# Channels_3_4.net
KiCad netlist of a schematic drawn in Altium Designer
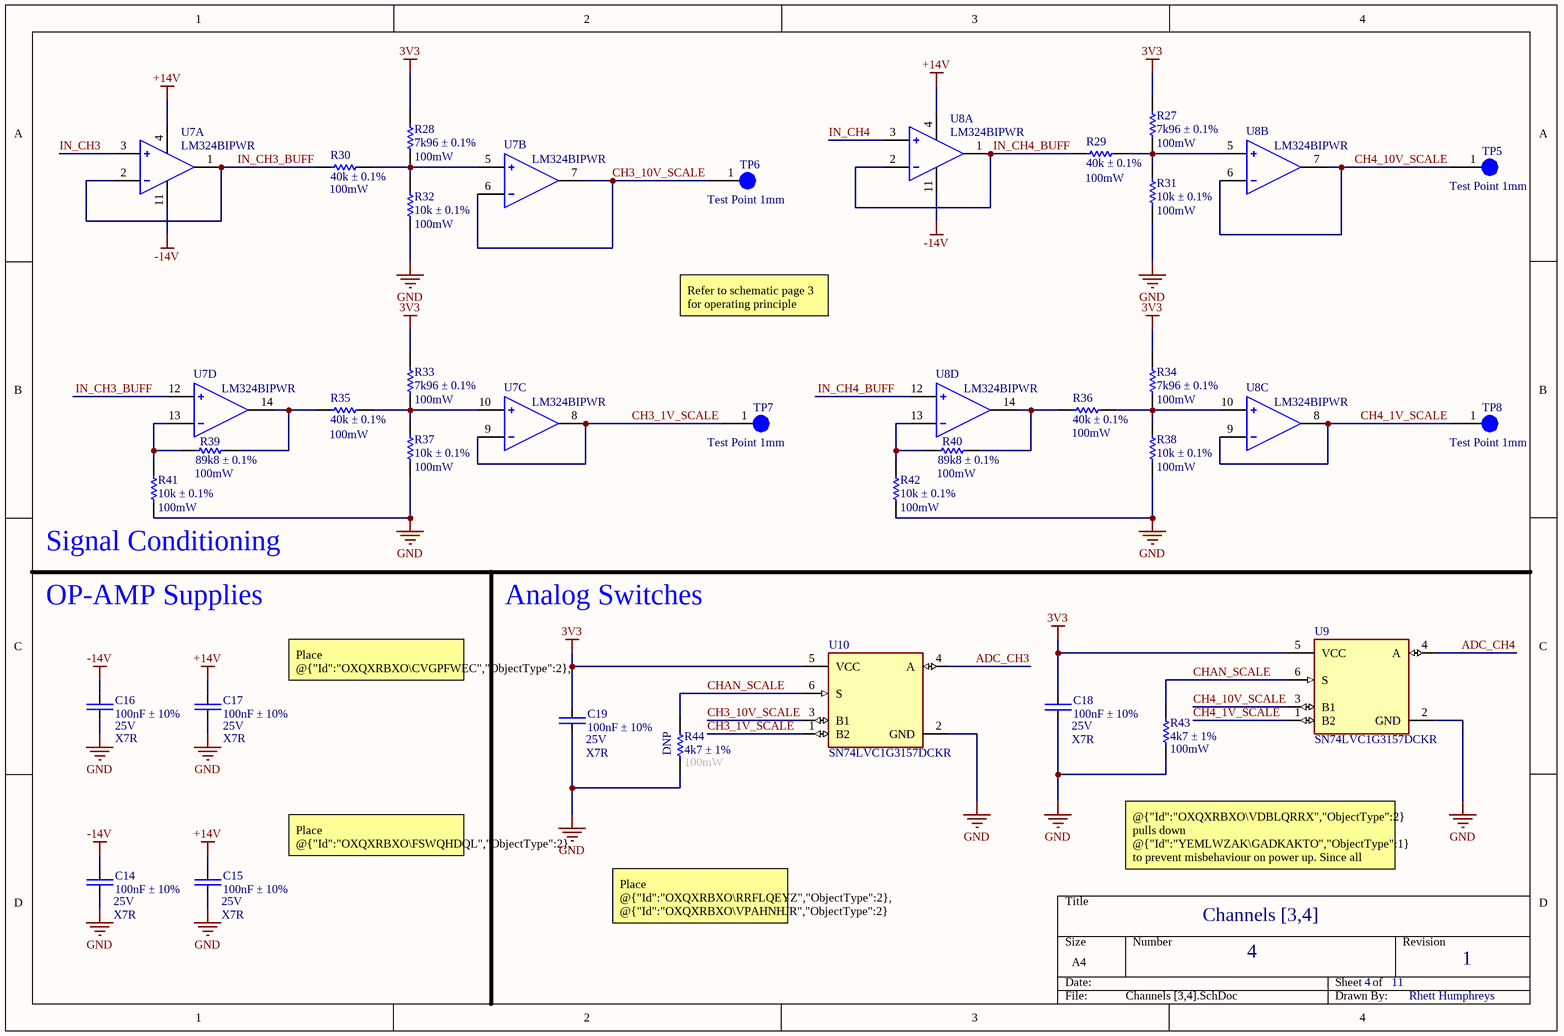
[diagram p0: Channels [3,4].SchDoc]

(export (version "E")
  (design (tool "Eeschema 10.0.6"))
  (components
    (comp (ref "C14")
      (value "100nF ± 10%")
      (footprint "CAP-0603")
      (description "Capacitor chip unpolarized. 0603")
      (libsource (lib "Master") (part "CAP-0603"))
    )
    (comp (ref "C15")
      (value "100nF ± 10%")
      (footprint "CAP-0603")
      (description "Capacitor chip unpolarized. 0603")
      (libsource (lib "Master") (part "CAP-0603"))
    )
    (comp (ref "C16")
      (value "100nF ± 10%")
      (footprint "CAP-0603")
      (description "Capacitor chip unpolarized. 0603")
      (libsource (lib "Master") (part "CAP-0603"))
    )
    (comp (ref "C17")
      (value "100nF ± 10%")
      (footprint "CAP-0603")
      (description "Capacitor chip unpolarized. 0603")
      (libsource (lib "Master") (part "CAP-0603"))
    )
    (comp (ref "C18")
      (value "100nF ± 10%")
      (footprint "CAP-0603")
      (description "Capacitor chip unpolarized. 0603")
      (libsource (lib "Master") (part "CAP-0603"))
    )
    (comp (ref "C19")
      (value "100nF ± 10%")
      (footprint "CAP-0603")
      (description "Capacitor chip unpolarized. 0603")
      (libsource (lib "Master") (part "CAP-0603"))
    )
    (comp (ref "R27")
      (value "7k96 ± 0.1%")
      (footprint "RES-0603")
      (description "Resistor chip. 0603")
      (libsource (lib "Master") (part "RES-0603"))
    )
    (comp (ref "R28")
      (value "7k96 ± 0.1%")
      (footprint "RES-0603")
      (description "Resistor chip. 0603")
      (libsource (lib "Master") (part "RES-0603"))
    )
    (comp (ref "R29")
      (value "40k ± 0.1%")
      (footprint "RES-0603")
      (description "Resistor chip. 0603")
      (libsource (lib "Master") (part "RES-0603"))
    )
    (comp (ref "R30")
      (value "40k ± 0.1%")
      (footprint "RES-0603")
      (description "Resistor chip. 0603")
      (libsource (lib "Master") (part "RES-0603"))
    )
    (comp (ref "R31")
      (value "10k ± 0.1%")
      (footprint "RES-0603")
      (description "Resistor chip. 0603")
      (libsource (lib "Master") (part "RES-0603"))
    )
    (comp (ref "R32")
      (value "10k ± 0.1%")
      (footprint "RES-0603")
      (description "Resistor chip. 0603")
      (libsource (lib "Master") (part "RES-0603"))
    )
    (comp (ref "R33")
      (value "7k96 ± 0.1%")
      (footprint "RES-0603")
      (description "Resistor chip. 0603")
      (libsource (lib "Master") (part "RES-0603"))
    )
    (comp (ref "R34")
      (value "7k96 ± 0.1%")
      (footprint "RES-0603")
      (description "Resistor chip. 0603")
      (libsource (lib "Master") (part "RES-0603"))
    )
    (comp (ref "R35")
      (value "40k ± 0.1%")
      (footprint "RES-0603")
      (description "Resistor chip. 0603")
      (libsource (lib "Master") (part "RES-0603"))
    )
    (comp (ref "R36")
      (value "40k ± 0.1%")
      (footprint "RES-0603")
      (description "Resistor chip. 0603")
      (libsource (lib "Master") (part "RES-0603"))
    )
    (comp (ref "R37")
      (value "10k ± 0.1%")
      (footprint "RES-0603")
      (description "Resistor chip. 0603")
      (libsource (lib "Master") (part "RES-0603"))
    )
    (comp (ref "R38")
      (value "10k ± 0.1%")
      (footprint "RES-0603")
      (description "Resistor chip. 0603")
      (libsource (lib "Master") (part "RES-0603"))
    )
    (comp (ref "R39")
      (value "89k8 ± 0.1%")
      (footprint "RES-0603")
      (description "Resistor chip. 0603")
      (libsource (lib "Master") (part "RES-0603"))
    )
    (comp (ref "R40")
      (value "89k8 ± 0.1%")
      (footprint "RES-0603")
      (description "Resistor chip. 0603")
      (libsource (lib "Master") (part "RES-0603"))
    )
    (comp (ref "R41")
      (value "10k ± 0.1%")
      (footprint "RES-0603")
      (description "Resistor chip. 0603")
      (libsource (lib "Master") (part "RES-0603"))
    )
    (comp (ref "R42")
      (value "10k ± 0.1%")
      (footprint "RES-0603")
      (description "Resistor chip. 0603")
      (libsource (lib "Master") (part "RES-0603"))
    )
    (comp (ref "R43")
      (value "4k7 ± 1%")
      (footprint "RES-0603")
      (description "Resistor chip. 0603")
      (libsource (lib "Master") (part "RES-0603"))
    )
    (comp (ref "R44")
      (value "4k7 ± 1%")
      (footprint "RES-0603")
      (description "Resistor chip. 0603")
      (libsource (lib "Master") (part "RES-0603"))
    )
    (comp (ref "TP5")
      (value "Test Point 1mm")
      (footprint "Test Point 1mm")
      (libsource (lib "Master") (part "Test Point 1mm"))
    )
    (comp (ref "TP6")
      (value "Test Point 1mm")
      (footprint "Test Point 1mm")
      (libsource (lib "Master") (part "Test Point 1mm"))
    )
    (comp (ref "TP7")
      (value "Test Point 1mm")
      (footprint "Test Point 1mm")
      (libsource (lib "Master") (part "Test Point 1mm"))
    )
    (comp (ref "TP8")
      (value "Test Point 1mm")
      (footprint "Test Point 1mm")
      (libsource (lib "Master") (part "Test Point 1mm"))
    )
    (comp (ref "U7")
      (value "LM324BIPWR")
      (footprint "FP-PW0014A-MFG")
      (description "LM324BIPWR Quad, 36-V, 1.2-MHz 3-mV offset voltage operational amplifier 14-TSSOP -40 to 85")
      (libsource (lib "Altium Content Vault") (part "9bf548ecc718f14caecb3de0839edcd"))
    )
    (comp (ref "U8")
      (value "LM324BIPWR")
      (footprint "FP-PW0014A-MFG")
      (description "LM324BIPWR Quad, 36-V, 1.2-MHz 3-mV offset voltage operational amplifier 14-TSSOP -40 to 85")
      (libsource (lib "Altium Content Vault") (part "9bf548ecc718f14caecb3de0839edcd"))
    )
    (comp (ref "U9")
      (value "SN74LVC1G3157DCKR")
      (footprint "FP-DCK0006A-IPC_B")
      (description "IC SWITCH SPDT SC70-6")
      (libsource (lib "Altium Content Vault") (part "0261a57985ab8eeec66806cf7caee19"))
    )
    (comp (ref "U10")
      (value "SN74LVC1G3157DCKR")
      (footprint "FP-DCK0006A-IPC_B")
      (description "IC SWITCH SPDT SC70-6")
      (libsource (lib "Altium Content Vault") (part "0261a57985ab8eeec66806cf7caee19"))
    )
  )
  (nets
    (net (code "1") (name "+14V") (class "Default")
      (node (ref "C15") (pin "2") (pintype "passive"))
      (node (ref "C17") (pin "2") (pintype "passive"))
      (node (ref "U7") (pin "4") (pinfunction "VCC+_4") (pintype "power_in"))
      (node (ref "U8") (pin "4") (pinfunction "VCC+_4") (pintype "power_in"))
    )
    (net (code "2") (name "-14V") (class "Default")
      (node (ref "C14") (pin "2") (pintype "passive"))
      (node (ref "C16") (pin "2") (pintype "passive"))
      (node (ref "U7") (pin "11") (pinfunction "VCC-_11") (pintype "power_in"))
      (node (ref "U8") (pin "11") (pinfunction "VCC-_11") (pintype "power_in"))
    )
    (net (code "3") (name "/ADC_CH3") (class "Default")
      (node (ref "U10") (pin "4") (pinfunction "A_4") (pintype "bidirectional"))
    )
    (net (code "4") (name "/ADC_CH4") (class "Default")
      (node (ref "U9") (pin "4") (pinfunction "A_4") (pintype "bidirectional"))
    )
    (net (code "5") (name "/CH3_1V_SCALE") (class "Default")
      (node (ref "TP7") (pin "1") (pintype "passive"))
      (node (ref "U10") (pin "1") (pinfunction "B2_1") (pintype "bidirectional"))
      (node (ref "U7") (pin "8") (pinfunction "3OUT_8") (pintype "passive"))
      (node (ref "U7") (pin "9") (pinfunction "3IN-_9") (pintype "tri_state"))
    )
    (net (code "6") (name "/CH3_10V_SCALE") (class "Default")
      (node (ref "TP6") (pin "1") (pintype "passive"))
      (node (ref "U10") (pin "3") (pinfunction "B1_3") (pintype "bidirectional"))
      (node (ref "U7") (pin "6") (pinfunction "2IN-_6") (pintype "tri_state"))
      (node (ref "U7") (pin "7") (pinfunction "2OUT_7") (pintype "passive"))
    )
    (net (code "7") (name "/CH4_1V_SCALE") (class "Default")
      (node (ref "TP8") (pin "1") (pintype "passive"))
      (node (ref "U8") (pin "8") (pinfunction "3OUT_8") (pintype "passive"))
      (node (ref "U8") (pin "9") (pinfunction "3IN-_9") (pintype "tri_state"))
      (node (ref "U9") (pin "1") (pinfunction "B2_1") (pintype "bidirectional"))
    )
    (net (code "8") (name "/CH4_10V_SCALE") (class "Default")
      (node (ref "TP5") (pin "1") (pintype "passive"))
      (node (ref "U8") (pin "6") (pinfunction "2IN-_6") (pintype "tri_state"))
      (node (ref "U8") (pin "7") (pinfunction "2OUT_7") (pintype "passive"))
      (node (ref "U9") (pin "3") (pinfunction "B1_3") (pintype "bidirectional"))
    )
    (net (code "9") (name "/CHAN_SCALE") (class "Default")
      (node (ref "R43") (pin "1") (pintype "passive"))
      (node (ref "R44") (pin "1") (pintype "passive"))
      (node (ref "U10") (pin "6") (pinfunction "S_6") (pintype "input"))
      (node (ref "U9") (pin "6") (pinfunction "S_6") (pintype "input"))
    )
    (net (code "10") (name "/IN_CH3") (class "Default")
      (node (ref "U7") (pin "3") (pinfunction "1IN+_3") (pintype "tri_state"))
    )
    (net (code "11") (name "/IN_CH3_BUFF") (class "Default")
      (node (ref "R30") (pin "2") (pintype "passive"))
      (node (ref "U7") (pin "1") (pinfunction "1OUT_1") (pintype "passive"))
      (node (ref "U7") (pin "12") (pinfunction "4IN+_12") (pintype "tri_state"))
      (node (ref "U7") (pin "2") (pinfunction "1IN-_2") (pintype "tri_state"))
    )
    (net (code "12") (name "/IN_CH4") (class "Default")
      (node (ref "U8") (pin "3") (pinfunction "1IN+_3") (pintype "tri_state"))
    )
    (net (code "13") (name "/IN_CH4_BUFF") (class "Default")
      (node (ref "R29") (pin "2") (pintype "passive"))
      (node (ref "U8") (pin "1") (pinfunction "1OUT_1") (pintype "passive"))
      (node (ref "U8") (pin "12") (pinfunction "4IN+_12") (pintype "tri_state"))
      (node (ref "U8") (pin "2") (pinfunction "1IN-_2") (pintype "tri_state"))
    )
    (net (code "14") (name "3V3") (class "Default")
      (node (ref "C18") (pin "2") (pintype "passive"))
      (node (ref "C19") (pin "2") (pintype "passive"))
      (node (ref "R27") (pin "1") (pintype "passive"))
      (node (ref "R28") (pin "1") (pintype "passive"))
      (node (ref "R33") (pin "1") (pintype "passive"))
      (node (ref "R34") (pin "1") (pintype "passive"))
      (node (ref "U10") (pin "5") (pinfunction "VCC_5") (pintype "power_in"))
      (node (ref "U9") (pin "5") (pinfunction "VCC_5") (pintype "power_in"))
    )
    (net (code "15") (name "GND") (class "Default")
      (node (ref "C14") (pin "1") (pintype "passive"))
      (node (ref "C15") (pin "1") (pintype "passive"))
      (node (ref "C16") (pin "1") (pintype "passive"))
      (node (ref "C17") (pin "1") (pintype "passive"))
      (node (ref "C18") (pin "1") (pintype "passive"))
      (node (ref "C19") (pin "1") (pintype "passive"))
      (node (ref "R31") (pin "2") (pintype "passive"))
      (node (ref "R32") (pin "2") (pintype "passive"))
      (node (ref "R37") (pin "2") (pintype "passive"))
      (node (ref "R38") (pin "2") (pintype "passive"))
      (node (ref "R41") (pin "2") (pintype "passive"))
      (node (ref "R42") (pin "2") (pintype "passive"))
      (node (ref "R43") (pin "2") (pintype "passive"))
      (node (ref "R44") (pin "2") (pintype "passive"))
      (node (ref "U10") (pin "2") (pinfunction "GND_2") (pintype "power_in"))
      (node (ref "U9") (pin "2") (pinfunction "GND_2") (pintype "power_in"))
    )
    (net (code "16") (name "Net-(U7B-2IN+)") (class "Default")
      (node (ref "R28") (pin "2") (pintype "passive"))
      (node (ref "R30") (pin "1") (pintype "passive"))
      (node (ref "R32") (pin "1") (pintype "passive"))
      (node (ref "U7") (pin "5") (pinfunction "2IN+_5") (pintype "tri_state"))
    )
    (net (code "17") (name "Net-(U7C-3IN+)") (class "Default")
      (node (ref "R33") (pin "2") (pintype "passive"))
      (node (ref "R35") (pin "1") (pintype "passive"))
      (node (ref "R37") (pin "1") (pintype "passive"))
      (node (ref "U7") (pin "10") (pinfunction "3IN+_10") (pintype "tri_state"))
    )
    (net (code "18") (name "Net-(U7D-4IN-)") (class "Default")
      (node (ref "R39") (pin "2") (pintype "passive"))
      (node (ref "R41") (pin "1") (pintype "passive"))
      (node (ref "U7") (pin "13") (pinfunction "4IN-_13") (pintype "tri_state"))
    )
    (net (code "19") (name "Net-(U7D-4OUT)") (class "Default")
      (node (ref "R35") (pin "2") (pintype "passive"))
      (node (ref "R39") (pin "1") (pintype "passive"))
      (node (ref "U7") (pin "14") (pinfunction "4OUT_14") (pintype "passive"))
    )
    (net (code "20") (name "Net-(U8B-2IN+)") (class "Default")
      (node (ref "R27") (pin "2") (pintype "passive"))
      (node (ref "R29") (pin "1") (pintype "passive"))
      (node (ref "R31") (pin "1") (pintype "passive"))
      (node (ref "U8") (pin "5") (pinfunction "2IN+_5") (pintype "tri_state"))
    )
    (net (code "21") (name "Net-(U8C-3IN+)") (class "Default")
      (node (ref "R34") (pin "2") (pintype "passive"))
      (node (ref "R36") (pin "1") (pintype "passive"))
      (node (ref "R38") (pin "1") (pintype "passive"))
      (node (ref "U8") (pin "10") (pinfunction "3IN+_10") (pintype "tri_state"))
    )
    (net (code "22") (name "Net-(U8D-4IN-)") (class "Default")
      (node (ref "R40") (pin "2") (pintype "passive"))
      (node (ref "R42") (pin "1") (pintype "passive"))
      (node (ref "U8") (pin "13") (pinfunction "4IN-_13") (pintype "tri_state"))
    )
    (net (code "23") (name "Net-(U8D-4OUT)") (class "Default")
      (node (ref "R36") (pin "2") (pintype "passive"))
      (node (ref "R40") (pin "1") (pintype "passive"))
      (node (ref "U8") (pin "14") (pinfunction "4OUT_14") (pintype "passive"))
    )
  )
)
